# speakermodule.net
KiCad netlist of a schematic drawn in EAGLE
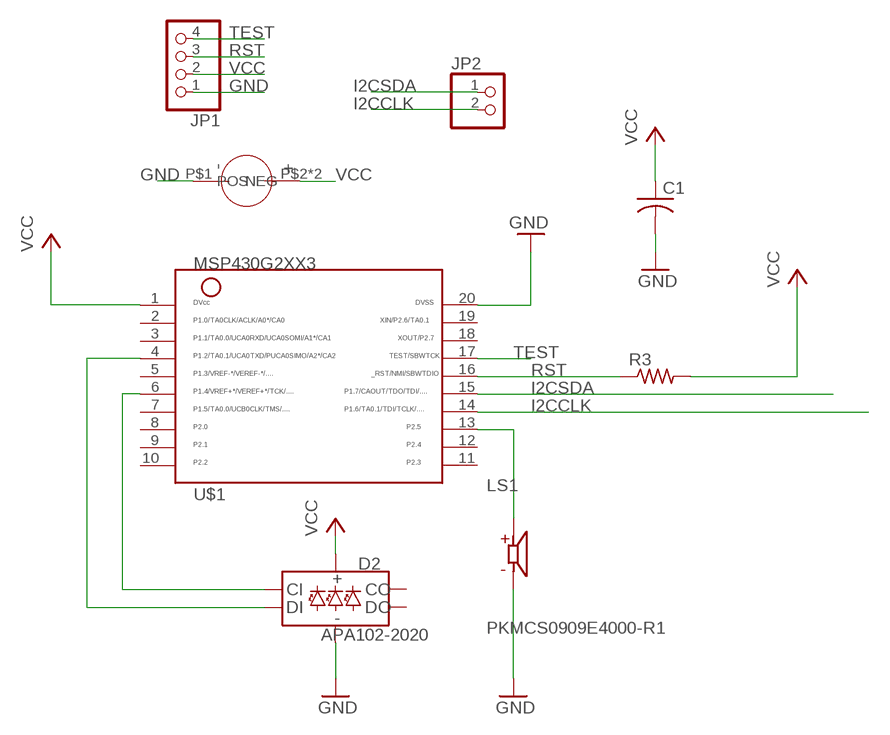
[diagram p0: schematic, sheet 1]

(export (version "E")
  (design (tool "Eeschema 10.0.6"))
  (components
    (comp (ref "C1")
      (value "C-USC1206")
      (footprint "eagle-import:C1206")
      (libsource (lib "eagle-import") (part "C-USC1206"))
    )
    (comp (ref "D2")
      (value "APA102-2020")
      (footprint "eagle-import:APA102-2020")
      (libsource (lib "eagle-import") (part "APA102-2020"))
    )
    (comp (ref "JP1")
      (value "PINHD-1X4")
      (footprint "eagle-import:1X04")
      (libsource (lib "eagle-import") (part "PINHD-1X4"))
    )
    (comp (ref "JP2")
      (value "PINHD-1X2")
      (footprint "eagle-import:1X02")
      (libsource (lib "eagle-import") (part "PINHD-1X2"))
    )
    (comp (ref "LS1")
      (value "PKMCS0909E4000-R1")
      (footprint "eagle-import:SPKR_PKMCS0909E4000-R1")
      (fields (field (name "DIGI-KEY_PART_NUMBER") "490-9647-1-ND") (field (name "MF") "Murata"))
      (libsource (lib "eagle-import") (part "PKMCS0909E4000-R1"))
    )
    (comp (ref "R3")
      (value "R-US_R1206")
      (footprint "eagle-import:R1206")
      (libsource (lib "eagle-import") (part "R-US_R1206"))
    )
    (comp (ref "U$1")
      (value "MSP430G2XX3TSSOP")
      (footprint "eagle-import:PW20")
      (libsource (lib "eagle-import") (part "MSP430G2XX3TSSOP"))
    )
    (comp (ref "U$3")
      (value "3002BATTERY")
      (footprint "eagle-import:3002BATTERY")
      (libsource (lib "eagle-import") (part "3002BATTERY"))
    )
  )
  (nets
    (net (code "1") (name "/I2CCLK") (class "Default")
      (node (ref "JP2") (pin "2") (pinfunction "2_2") (pintype "passive"))
      (node (ref "U$1") (pin "14") (pinfunction "14_14") (pintype "bidirectional"))
    )
    (net (code "2") (name "/I2CSDA") (class "Default")
      (node (ref "JP2") (pin "1") (pinfunction "1_1") (pintype "passive"))
      (node (ref "U$1") (pin "15") (pinfunction "15_15") (pintype "bidirectional"))
    )
    (net (code "3") (name "/RST") (class "Default")
      (node (ref "JP1") (pin "3") (pinfunction "3_3") (pintype "passive"))
      (node (ref "R3") (pin "1") (pinfunction "1_1") (pintype "passive"))
      (node (ref "U$1") (pin "16") (pinfunction "16_16") (pintype "bidirectional"))
    )
    (net (code "4") (name "/TEST") (class "Default")
      (node (ref "JP1") (pin "4") (pinfunction "4_4") (pintype "passive"))
      (node (ref "U$1") (pin "17") (pinfunction "17_17") (pintype "bidirectional"))
    )
    (net (code "5") (name "GND") (class "Default")
      (node (ref "C1") (pin "2") (pinfunction "2_2") (pintype "passive"))
      (node (ref "D2") (pin "GND") (pinfunction "GND_GND") (pintype "bidirectional"))
      (node (ref "JP1") (pin "1") (pinfunction "1_1") (pintype "passive"))
      (node (ref "LS1") (pin "2") (pinfunction "N_2") (pintype "passive"))
      (node (ref "U$1") (pin "20") (pinfunction "20_20") (pintype "bidirectional"))
      (node (ref "U$3") (pin "P$1") (pinfunction "NEG_P$1") (pintype "bidirectional"))
    )
    (net (code "6") (name "Net-(D2-CI)") (class "Default")
      (node (ref "D2") (pin "CKI") (pinfunction "CI_CKI") (pintype "bidirectional"))
      (node (ref "U$1") (pin "6") (pinfunction "6_6") (pintype "bidirectional"))
    )
    (net (code "7") (name "Net-(D2-DI)") (class "Default")
      (node (ref "D2") (pin "SDI") (pinfunction "DI_SDI") (pintype "bidirectional"))
      (node (ref "U$1") (pin "4") (pinfunction "4_4") (pintype "bidirectional"))
    )
    (net (code "8") (name "Net-(LS1-P)") (class "Default")
      (node (ref "LS1") (pin "1") (pinfunction "P_1") (pintype "passive"))
      (node (ref "U$1") (pin "13") (pinfunction "13_13") (pintype "bidirectional"))
    )
    (net (code "9") (name "VCC") (class "Default")
      (node (ref "C1") (pin "1") (pinfunction "1_1") (pintype "passive"))
      (node (ref "D2") (pin "VDD") (pinfunction "VCC_VDD") (pintype "bidirectional"))
      (node (ref "JP1") (pin "2") (pinfunction "2_2") (pintype "passive"))
      (node (ref "R3") (pin "2") (pinfunction "2_2") (pintype "passive"))
      (node (ref "U$1") (pin "1") (pinfunction "1_1") (pintype "bidirectional"))
      (node (ref "U$3") (pin "P$2") (pinfunction "POS_P$2") (pintype "bidirectional"))
      (node (ref "U$3") (pin "P$3") (pinfunction "POS_P$3") (pintype "bidirectional"))
    )
    (net (code "10") (name "unconnected-(D2-CO-PadCKO)") (class "Default")
      (node (ref "D2") (pin "CKO") (pinfunction "CO_CKO") (pintype "bidirectional"))
    )
    (net (code "11") (name "unconnected-(D2-DO-PadSDO)") (class "Default")
      (node (ref "D2") (pin "SDO") (pinfunction "DO_SDO") (pintype "bidirectional"))
    )
    (net (code "12") (name "unconnected-(U$1-Pad2)") (class "Default")
      (node (ref "U$1") (pin "2") (pinfunction "2_2") (pintype "bidirectional"))
    )
    (net (code "13") (name "unconnected-(U$1-Pad3)") (class "Default")
      (node (ref "U$1") (pin "3") (pinfunction "3_3") (pintype "bidirectional"))
    )
    (net (code "14") (name "unconnected-(U$1-Pad5)") (class "Default")
      (node (ref "U$1") (pin "5") (pinfunction "5_5") (pintype "bidirectional"))
    )
    (net (code "15") (name "unconnected-(U$1-Pad7)") (class "Default")
      (node (ref "U$1") (pin "7") (pinfunction "7_7") (pintype "bidirectional"))
    )
    (net (code "16") (name "unconnected-(U$1-Pad8)") (class "Default")
      (node (ref "U$1") (pin "8") (pinfunction "8_8") (pintype "bidirectional"))
    )
    (net (code "17") (name "unconnected-(U$1-Pad9)") (class "Default")
      (node (ref "U$1") (pin "9") (pinfunction "9_9") (pintype "bidirectional"))
    )
    (net (code "18") (name "unconnected-(U$1-Pad10)") (class "Default")
      (node (ref "U$1") (pin "10") (pinfunction "10_10") (pintype "bidirectional"))
    )
    (net (code "19") (name "unconnected-(U$1-Pad11)") (class "Default")
      (node (ref "U$1") (pin "11") (pinfunction "11_11") (pintype "bidirectional"))
    )
    (net (code "20") (name "unconnected-(U$1-Pad12)") (class "Default")
      (node (ref "U$1") (pin "12") (pinfunction "12_12") (pintype "bidirectional"))
    )
    (net (code "21") (name "unconnected-(U$1-Pad18)") (class "Default")
      (node (ref "U$1") (pin "18") (pinfunction "18_18") (pintype "bidirectional"))
    )
    (net (code "22") (name "unconnected-(U$1-Pad19)") (class "Default")
      (node (ref "U$1") (pin "19") (pinfunction "19_19") (pintype "bidirectional"))
    )
  )
)
